# DRUM_1_MAIN_6.net
KiCad netlist of a schematic drawn in EAGLE
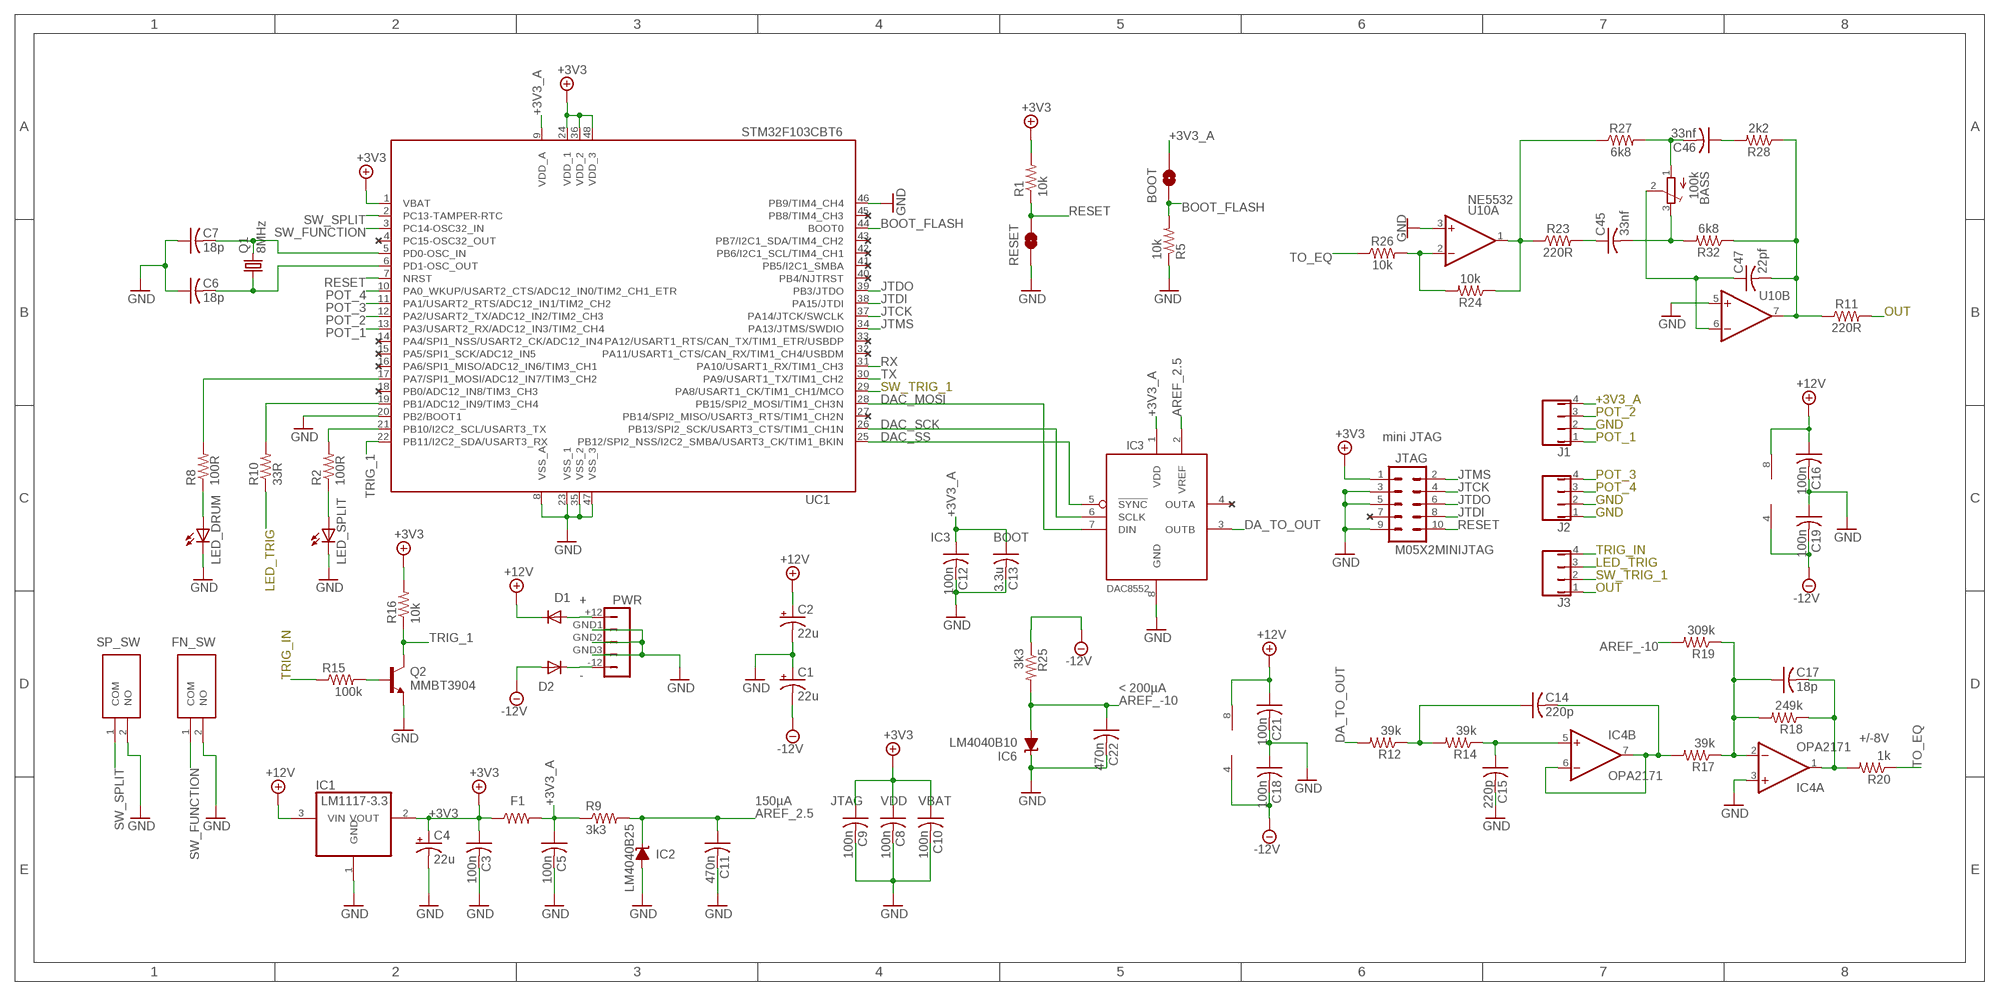
[diagram p0: schematic, sheet 1]

(export (version "E")
  (design (tool "Eeschema 10.0.6"))
  (components
    (comp (ref "BASS")
      (value "100k")
      (footprint "eagle-import:ADAFRUIT_TC33X")
      (libsource (lib "eagle-import") (part "ADAFRUIT_TRIMPOTTC33X"))
    )
    (comp (ref "BOOT")
      (value "BOOT")
      (footprint "eagle-import:SMT-JUMPER_2_NO_SILK")
      (libsource (lib "eagle-import") (part "JUMPER-SMT_2_NO_SILK"))
    )
    (comp (ref "C1")
      (value "22u")
      (footprint "eagle-import:PANASONIC_C")
      (libsource (lib "eagle-import") (part "CPOL-USC"))
    )
    (comp (ref "C2")
      (value "22u")
      (footprint "eagle-import:PANASONIC_C")
      (libsource (lib "eagle-import") (part "CPOL-USC"))
    )
    (comp (ref "C3")
      (value "100n")
      (footprint "eagle-import:C0603")
      (libsource (lib "eagle-import") (part "AA_Stobbert_1_C-USC0603"))
    )
    (comp (ref "C4")
      (value "22u")
      (footprint "eagle-import:PANASONIC_C")
      (libsource (lib "eagle-import") (part "CPOL-USC"))
    )
    (comp (ref "C5")
      (value "100n")
      (footprint "eagle-import:C0603")
      (libsource (lib "eagle-import") (part "AA_Stobbert_1_C-USC0603"))
    )
    (comp (ref "C6")
      (value "18p")
      (footprint "eagle-import:C0603")
      (libsource (lib "eagle-import") (part "AA_Stobbert_1_C-USC0603"))
    )
    (comp (ref "C7")
      (value "18p")
      (footprint "eagle-import:C0603")
      (libsource (lib "eagle-import") (part "AA_Stobbert_1_C-USC0603"))
    )
    (comp (ref "C8")
      (value "100n")
      (footprint "eagle-import:C0603")
      (libsource (lib "eagle-import") (part "AA_Stobbert_1_C-USC0603"))
    )
    (comp (ref "C9")
      (value "100n")
      (footprint "eagle-import:C0603")
      (libsource (lib "eagle-import") (part "AA_Stobbert_1_C-USC0603"))
    )
    (comp (ref "C10")
      (value "100n")
      (footprint "eagle-import:C0603")
      (libsource (lib "eagle-import") (part "AA_Stobbert_1_C-USC0603"))
    )
    (comp (ref "C11")
      (value "470n")
      (footprint "eagle-import:C0603")
      (libsource (lib "eagle-import") (part "AA_Stobbert_1_C-USC0603"))
    )
    (comp (ref "C12")
      (value "100n")
      (footprint "eagle-import:C0603")
      (libsource (lib "eagle-import") (part "AA_Stobbert_1_C-USC0603"))
    )
    (comp (ref "C13")
      (value "3.3u")
      (footprint "eagle-import:C0805K")
      (libsource (lib "eagle-import") (part "AA_Stobbert_1_C-USC0805K"))
    )
    (comp (ref "C14")
      (value "220p")
      (footprint "eagle-import:C0603")
      (libsource (lib "eagle-import") (part "AA_Stobbert_1_C-USC0603"))
    )
    (comp (ref "C15")
      (value "220p")
      (footprint "eagle-import:C0603")
      (libsource (lib "eagle-import") (part "AA_Stobbert_1_C-USC0603"))
    )
    (comp (ref "C16")
      (value "100n")
      (footprint "eagle-import:C0603")
      (libsource (lib "eagle-import") (part "AA_Stobbert_1_C-USC0603"))
    )
    (comp (ref "C17")
      (value "18p")
      (footprint "eagle-import:C0603")
      (libsource (lib "eagle-import") (part "AA_Stobbert_1_C-USC0603"))
    )
    (comp (ref "C18")
      (value "100n")
      (footprint "eagle-import:C0603")
      (libsource (lib "eagle-import") (part "AA_Stobbert_1_C-USC0603"))
    )
    (comp (ref "C19")
      (value "100n")
      (footprint "eagle-import:C0603")
      (libsource (lib "eagle-import") (part "AA_Stobbert_1_C-USC0603"))
    )
    (comp (ref "C21")
      (value "100n")
      (footprint "eagle-import:C0603")
      (libsource (lib "eagle-import") (part "AA_Stobbert_1_C-USC0603"))
    )
    (comp (ref "C22")
      (value "470n")
      (footprint "eagle-import:C0603")
      (libsource (lib "eagle-import") (part "AA_Stobbert_1_C-USC0603"))
    )
    (comp (ref "C45")
      (value "33nf")
      (footprint "eagle-import:C0603")
      (libsource (lib "eagle-import") (part "C-USC0603"))
    )
    (comp (ref "C46")
      (value "33nf")
      (footprint "eagle-import:C0603")
      (libsource (lib "eagle-import") (part "AA_Stobbert_1_C-USC0603"))
    )
    (comp (ref "C47")
      (value "22pf")
      (footprint "eagle-import:C0603")
      (libsource (lib "eagle-import") (part "C-USC0603"))
    )
    (comp (ref "D1")
      (value "1N5819HW")
      (footprint "eagle-import:PNS40010ER_SOD123W")
      (libsource (lib "eagle-import") (part "PWR_DIODE"))
    )
    (comp (ref "D2")
      (value "1N5819HW")
      (footprint "eagle-import:PNS40010ER_SOD123W")
      (libsource (lib "eagle-import") (part "PWR_DIODE"))
    )
    (comp (ref "F1")
      (value "742792693")
      (footprint "eagle-import:R0603")
      (libsource (lib "eagle-import") (part "R-US_R0603"))
    )
    (comp (ref "FN_SW")
      (value "PTS636_SM25_SMTR_LFS C778169")
      (footprint "eagle-import:PTS636SM25SMTRLFS")
      (fields
        (field (name "MANUFACTURER_PART_NUMBER") "PTS636 SM25 SMTR LFS")
        (field (name "MOUSER_PART_NUMBER") "611-PTS636SM25SMTRLF")
      )
      (libsource (lib "eagle-import") (part "PTS636_SM25_SMTR_LFS"))
    )
    (comp (ref "IC1")
      (value "LM1117-3.3")
      (footprint "eagle-import:SOT223")
      (libsource (lib "eagle-import") (part "REG1117"))
    )
    (comp (ref "IC2")
      (value "LM4040B25")
      (footprint "eagle-import:DBZ_R-PDSO-G3")
      (libsource (lib "eagle-import") (part "LM4041DBZB12"))
    )
    (comp (ref "IC3")
      (value "DAC8552")
      (footprint "eagle-import:MSOP-8")
      (libsource (lib "eagle-import") (part "DAC8552"))
    )
    (comp (ref "IC4")
      (value "OPA2171")
      (footprint "eagle-import:SO08")
      (libsource (lib "eagle-import") (part "linear_TL072D"))
    )
    (comp (ref "IC6")
      (value "LM4040B10")
      (footprint "eagle-import:DBZ_R-PDSO-G3")
      (libsource (lib "eagle-import") (part "LM4041DBZB12"))
    )
    (comp (ref "J1")
      (value "1x4 FEMALE HEADER")
      (footprint "eagle-import:JMP_4P_SIP")
      (libsource (lib "eagle-import") (part "JMP/4P/SIP"))
    )
    (comp (ref "J2")
      (value "1x4 FEMALE HEADER")
      (footprint "eagle-import:JMP_4P_SIP")
      (libsource (lib "eagle-import") (part "JMP/4P/SIP"))
    )
    (comp (ref "J3")
      (value "1x4 FEMALE HEADER")
      (footprint "eagle-import:JMP_4P_SIP")
      (libsource (lib "eagle-import") (part "JMP/4P/SIP"))
    )
    (comp (ref "JTAG")
      (value "M05X2MINIJTAG")
      (footprint "eagle-import:2X5-1.27")
      (libsource (lib "eagle-import") (part "M05X2MINIJTAG"))
    )
    (comp (ref "LED_DRUM")
      (value "LEDS0805")
      (footprint "eagle-import:LED_0805A")
      (libsource (lib "eagle-import") (part "LEDS0805"))
    )
    (comp (ref "LED_SPLIT")
      (value "LEDS0805")
      (footprint "eagle-import:LED_0805A")
      (libsource (lib "eagle-import") (part "LEDS0805"))
    )
    (comp (ref "PWR")
      (value "JMP/5P/DIP1X5_HEADER")
      (footprint "eagle-import:JMP_5P_DIP")
      (libsource (lib "eagle-import") (part "JMP/5P/DIP1X5_HEADER"))
    )
    (comp (ref "Q1")
      (value "8MHz")
      (footprint "eagle-import:HC49UP")
      (libsource (lib "eagle-import") (part "CRYSTALHC49UP"))
    )
    (comp (ref "Q2")
      (value "MMBT3904")
      (footprint "eagle-import:SOT23-BEC")
      (libsource (lib "eagle-import") (part "-NPN-SOT23-BECMMBT3904LT1"))
    )
    (comp (ref "R1")
      (value "10k")
      (footprint "eagle-import:R0603")
      (libsource (lib "eagle-import") (part "R-US_R0603"))
    )
    (comp (ref "R2")
      (value "100R")
      (footprint "eagle-import:R0603")
      (libsource (lib "eagle-import") (part "R-US_R0603"))
    )
    (comp (ref "R5")
      (value "10k")
      (footprint "eagle-import:R0603")
      (libsource (lib "eagle-import") (part "R-US_R0603"))
    )
    (comp (ref "R8")
      (value "100R")
      (footprint "eagle-import:R0603")
      (libsource (lib "eagle-import") (part "R-US_R0603"))
    )
    (comp (ref "R9")
      (value "3k3")
      (footprint "eagle-import:R0603")
      (libsource (lib "eagle-import") (part "R-US_R0603"))
    )
    (comp (ref "R10")
      (value "33R")
      (footprint "eagle-import:R0603")
      (libsource (lib "eagle-import") (part "R-US_R0603"))
    )
    (comp (ref "R11")
      (value "220R")
      (footprint "eagle-import:R0603")
      (libsource (lib "eagle-import") (part "R-US_R0603"))
    )
    (comp (ref "R12")
      (value "39k")
      (footprint "eagle-import:R0603")
      (libsource (lib "eagle-import") (part "R-US_R0603"))
    )
    (comp (ref "R14")
      (value "39k")
      (footprint "eagle-import:R0603")
      (libsource (lib "eagle-import") (part "R-US_R0603"))
    )
    (comp (ref "R15")
      (value "100k")
      (footprint "eagle-import:R0603")
      (libsource (lib "eagle-import") (part "R-US_R0603"))
    )
    (comp (ref "R16")
      (value "10k")
      (footprint "eagle-import:R0603")
      (libsource (lib "eagle-import") (part "R-US_R0603"))
    )
    (comp (ref "R17")
      (value "39k")
      (footprint "eagle-import:R0603")
      (libsource (lib "eagle-import") (part "R-US_R0603"))
    )
    (comp (ref "R18")
      (value "249k")
      (footprint "eagle-import:R0603")
      (libsource (lib "eagle-import") (part "R-US_R0603"))
    )
    (comp (ref "R19")
      (value "309k")
      (footprint "eagle-import:R0603")
      (libsource (lib "eagle-import") (part "R-US_R0603"))
    )
    (comp (ref "R20")
      (value "1k")
      (footprint "eagle-import:R0603")
      (libsource (lib "eagle-import") (part "R-US_R0603"))
    )
    (comp (ref "R23")
      (value "220R")
      (footprint "eagle-import:R0603")
      (libsource (lib "eagle-import") (part "R-US_R0603"))
    )
    (comp (ref "R24")
      (value "10k")
      (footprint "eagle-import:R0603")
      (libsource (lib "eagle-import") (part "R-US_R0603"))
    )
    (comp (ref "R25")
      (value "3k3")
      (footprint "eagle-import:R0603")
      (libsource (lib "eagle-import") (part "R-US_R0603"))
    )
    (comp (ref "R26")
      (value "10k")
      (footprint "eagle-import:R0603")
      (libsource (lib "eagle-import") (part "R-US_R0603"))
    )
    (comp (ref "R27")
      (value "6k8")
      (footprint "eagle-import:R0603")
      (libsource (lib "eagle-import") (part "R-US_R0603"))
    )
    (comp (ref "R28")
      (value "2k2")
      (footprint "eagle-import:R0603")
      (libsource (lib "eagle-import") (part "R-US_R0603"))
    )
    (comp (ref "R32")
      (value "6k8")
      (footprint "eagle-import:R0603")
      (libsource (lib "eagle-import") (part "R-US_R0603"))
    )
    (comp (ref "RESET")
      (value "RESET")
      (footprint "eagle-import:SMT-JUMPER_2_NO_SILK")
      (libsource (lib "eagle-import") (part "JUMPER-SMT_2_NO_SILK"))
    )
    (comp (ref "SP_SW")
      (value "PTS636_SM25_SMTR_LFS C778169")
      (footprint "eagle-import:PTS636SM25SMTRLFS")
      (fields
        (field (name "MANUFACTURER_PART_NUMBER") "PTS636 SM25 SMTR LFS")
        (field (name "MOUSER_PART_NUMBER") "611-PTS636SM25SMTRLF")
      )
      (libsource (lib "eagle-import") (part "PTS636_SM25_SMTR_LFS"))
    )
    (comp (ref "U10")
      (value "NE5532")
      (footprint "eagle-import:SO08")
      (libsource (lib "eagle-import") (part "TL072D"))
    )
    (comp (ref "UC1")
      (value "STM32F103CBT6")
      (footprint "eagle-import:LQFP48")
      (libsource (lib "eagle-import") (part "STM32F103CB"))
    )
  )
  (nets
    (net (code "1") (name "+3V3") (class "Default")
      (node (ref "C10") (pin "1") (pinfunction "1_1") (pintype "passive"))
      (node (ref "C3") (pin "1") (pinfunction "1_1") (pintype "passive"))
      (node (ref "C4") (pin "+") (pinfunction "+_+") (pintype "passive"))
      (node (ref "C8") (pin "1") (pinfunction "1_1") (pintype "passive"))
      (node (ref "C9") (pin "1") (pinfunction "1_1") (pintype "passive"))
      (node (ref "F1") (pin "1") (pinfunction "1_1") (pintype "passive"))
      (node (ref "IC1") (pin "2") (pinfunction "VOUT_2") (pintype "output"))
      (node (ref "JTAG") (pin "1") (pinfunction "1_1") (pintype "passive"))
      (node (ref "R1") (pin "2") (pinfunction "2_2") (pintype "passive"))
      (node (ref "R16") (pin "2") (pinfunction "2_2") (pintype "passive"))
      (node (ref "UC1") (pin "1") (pinfunction "VBAT_1") (pintype "power_in"))
      (node (ref "UC1") (pin "24") (pinfunction "VDD_1_24") (pintype "power_in"))
      (node (ref "UC1") (pin "36") (pinfunction "VDD_2_36") (pintype "power_in"))
      (node (ref "UC1") (pin "48") (pinfunction "VDD_3_48") (pintype "power_in"))
    )
    (net (code "2") (name "+12V") (class "Default")
      (node (ref "C16") (pin "1") (pinfunction "1_1") (pintype "passive"))
      (node (ref "C2") (pin "+") (pinfunction "+_+") (pintype "passive"))
      (node (ref "C21") (pin "1") (pinfunction "1_1") (pintype "passive"))
      (node (ref "D1") (pin "1") (pinfunction "K_1") (pintype "passive"))
      (node (ref "IC1") (pin "3") (pinfunction "VIN_3") (pintype "input"))
      (node (ref "IC4") (pin "8") (pinfunction "V+_8") (pintype "power_in"))
      (node (ref "U10") (pin "8") (pinfunction "V+_8") (pintype "power_in"))
    )
    (net (code "3") (name "-12V") (class "Default")
      (node (ref "C1") (pin "-") (pinfunction "-_-") (pintype "passive"))
      (node (ref "C18") (pin "2") (pinfunction "2_2") (pintype "passive"))
      (node (ref "C19") (pin "2") (pinfunction "2_2") (pintype "passive"))
      (node (ref "D2") (pin "2") (pinfunction "A_2") (pintype "passive"))
      (node (ref "IC4") (pin "4") (pinfunction "V-_4") (pintype "power_in"))
      (node (ref "R25") (pin "1") (pinfunction "1_1") (pintype "passive"))
      (node (ref "U10") (pin "4") (pinfunction "V-_4") (pintype "power_in"))
    )
    (net (code "4") (name "/+") (class "Default")
      (node (ref "D1") (pin "2") (pinfunction "A_2") (pintype "passive"))
      (node (ref "PWR") (pin "+12") (pinfunction "+12_+12") (pintype "passive"))
    )
    (net (code "5") (name "/+3V3_A") (class "Default")
      (node (ref "BOOT") (pin "2") (pinfunction "2_2") (pintype "passive"))
      (node (ref "C12") (pin "1") (pinfunction "1_1") (pintype "passive"))
      (node (ref "C13") (pin "1") (pinfunction "1_1") (pintype "passive"))
      (node (ref "C5") (pin "1") (pinfunction "1_1") (pintype "passive"))
      (node (ref "F1") (pin "2") (pinfunction "2_2") (pintype "passive"))
      (node (ref "IC3") (pin "1") (pinfunction "VDD_1") (pintype "power_in"))
      (node (ref "J1") (pin "4") (pinfunction "4_4") (pintype "passive"))
      (node (ref "R9") (pin "1") (pinfunction "1_1") (pintype "passive"))
      (node (ref "UC1") (pin "9") (pinfunction "VDD_A_9") (pintype "power_in"))
    )
    (net (code "6") (name "/-") (class "Default")
      (node (ref "D2") (pin "1") (pinfunction "K_1") (pintype "passive"))
      (node (ref "PWR") (pin "-12") (pinfunction "-12_-12") (pintype "passive"))
    )
    (net (code "7") (name "/AREF_-10") (class "Default")
      (node (ref "C22") (pin "1") (pinfunction "1_1") (pintype "passive"))
      (node (ref "IC6") (pin "2") (pinfunction "A_2") (pintype "passive"))
      (node (ref "R19") (pin "2") (pinfunction "2_2") (pintype "passive"))
      (node (ref "R25") (pin "2") (pinfunction "2_2") (pintype "passive"))
    )
    (net (code "8") (name "/AREF_2.5") (class "Default")
      (node (ref "C11") (pin "1") (pinfunction "1_1") (pintype "passive"))
      (node (ref "IC2") (pin "1") (pinfunction "C_1") (pintype "passive"))
      (node (ref "IC3") (pin "2") (pinfunction "VREF_2") (pintype "power_in"))
      (node (ref "R9") (pin "2") (pinfunction "2_2") (pintype "passive"))
    )
    (net (code "9") (name "/BOOT_FLASH") (class "Default")
      (node (ref "BOOT") (pin "1") (pinfunction "1_1") (pintype "passive"))
      (node (ref "R5") (pin "2") (pinfunction "2_2") (pintype "passive"))
      (node (ref "UC1") (pin "44") (pinfunction "BOOT0_44") (pintype "input"))
    )
    (net (code "10") (name "/DAC_MOSI") (class "Default")
      (node (ref "IC3") (pin "7") (pinfunction "DIN_7") (pintype "bidirectional"))
      (node (ref "UC1") (pin "28") (pinfunction "PB15/SPI2_MOSI/TIM1_CH3N_28") (pintype "input"))
    )
    (net (code "11") (name "/DAC_SCK") (class "Default")
      (node (ref "IC3") (pin "6") (pinfunction "SCLK_6") (pintype "bidirectional"))
      (node (ref "UC1") (pin "26") (pinfunction "PB13/SPI2_SCK/USART3_CTS/TIM1_CH1N_26") (pintype "input"))
    )
    (net (code "12") (name "/DAC_SS") (class "Default")
      (node (ref "IC3") (pin "5") (pinfunction "~{SYNC}_5") (pintype "bidirectional"))
      (node (ref "UC1") (pin "25") (pinfunction "PB12/SPI2_NSS/I2C2_SMBA/USART3_CK/TIM1_BKIN_25") (pintype "input"))
    )
    (net (code "13") (name "/DA_TO_OUT") (class "Default")
      (node (ref "IC3") (pin "3") (pinfunction "OUTB_3") (pintype "input"))
      (node (ref "R12") (pin "2") (pinfunction "2_2") (pintype "passive"))
    )
    (net (code "14") (name "/JTCK") (class "Default")
      (node (ref "JTAG") (pin "4") (pinfunction "4_4") (pintype "passive"))
      (node (ref "UC1") (pin "37") (pinfunction "PA14/JTCK/SWCLK_37") (pintype "bidirectional"))
    )
    (net (code "15") (name "/JTDI") (class "Default")
      (node (ref "JTAG") (pin "8") (pinfunction "8_8") (pintype "passive"))
      (node (ref "UC1") (pin "38") (pinfunction "PA15/JTDI_38") (pintype "bidirectional"))
    )
    (net (code "16") (name "/JTDO") (class "Default")
      (node (ref "JTAG") (pin "6") (pinfunction "6_6") (pintype "passive"))
      (node (ref "UC1") (pin "39") (pinfunction "PB3/JTDO_39") (pintype "bidirectional"))
    )
    (net (code "17") (name "/JTMS") (class "Default")
      (node (ref "JTAG") (pin "2") (pinfunction "2_2") (pintype "passive"))
      (node (ref "UC1") (pin "34") (pinfunction "PA13/JTMS/SWDIO_34") (pintype "bidirectional"))
    )
    (net (code "18") (name "/LED_TRIG") (class "Default")
      (node (ref "J3") (pin "3") (pinfunction "3_3") (pintype "passive"))
      (node (ref "R10") (pin "1") (pinfunction "1_1") (pintype "passive"))
    )
    (net (code "19") (name "/OUT") (class "Default")
      (node (ref "J3") (pin "1") (pinfunction "1_1") (pintype "passive"))
      (node (ref "R11") (pin "2") (pinfunction "2_2") (pintype "passive"))
    )
    (net (code "20") (name "/POT_1") (class "Default")
      (node (ref "J1") (pin "1") (pinfunction "1_1") (pintype "passive"))
      (node (ref "UC1") (pin "13") (pinfunction "PA3/USART2_RX/ADC12_IN3/TIM2_CH4_13") (pintype "bidirectional"))
    )
    (net (code "21") (name "/POT_2") (class "Default")
      (node (ref "J1") (pin "3") (pinfunction "3_3") (pintype "passive"))
      (node (ref "UC1") (pin "12") (pinfunction "PA2/USART2_TX/ADC12_IN2/TIM2_CH3_12") (pintype "bidirectional"))
    )
    (net (code "22") (name "/POT_3") (class "Default")
      (node (ref "J2") (pin "4") (pinfunction "4_4") (pintype "passive"))
      (node (ref "UC1") (pin "11") (pinfunction "PA1/USART2_RTS/ADC12_IN1/TIM2_CH2_11") (pintype "bidirectional"))
    )
    (net (code "23") (name "/POT_4") (class "Default")
      (node (ref "J2") (pin "3") (pinfunction "3_3") (pintype "passive"))
      (node (ref "UC1") (pin "10") (pinfunction "PA0_WKUP/USART2_CTS/ADC12_IN0/TIM2_CH1_ETR_10") (pintype "bidirectional"))
    )
    (net (code "24") (name "/RESET") (class "Default")
      (node (ref "JTAG") (pin "10") (pinfunction "10_10") (pintype "passive"))
      (node (ref "R1") (pin "1") (pinfunction "1_1") (pintype "passive"))
      (node (ref "RESET") (pin "2") (pinfunction "2_2") (pintype "passive"))
      (node (ref "UC1") (pin "7") (pinfunction "NRST_7") (pintype "input"))
    )
    (net (code "25") (name "/RX") (class "Default")
      (node (ref "UC1") (pin "31") (pinfunction "PA10/USART1_RX/TIM1_CH3_31") (pintype "bidirectional"))
    )
    (net (code "26") (name "/SW_FUNCTION") (class "Default")
      (node (ref "FN_SW") (pin "1") (pinfunction "COM_1") (pintype "bidirectional"))
      (node (ref "UC1") (pin "3") (pinfunction "PC14-OSC32_IN_3") (pintype "input"))
    )
    (net (code "27") (name "/SW_SPLIT") (class "Default")
      (node (ref "SP_SW") (pin "1") (pinfunction "COM_1") (pintype "bidirectional"))
      (node (ref "UC1") (pin "2") (pinfunction "PC13-TAMPER-RTC_2") (pintype "input"))
    )
    (net (code "28") (name "/SW_TRIG_1") (class "Default")
      (node (ref "J3") (pin "2") (pinfunction "2_2") (pintype "passive"))
      (node (ref "UC1") (pin "29") (pinfunction "PA8/USART1_CK/TIM1_CH1/MCO_29") (pintype "bidirectional"))
    )
    (net (code "29") (name "/TO_EQ") (class "Default")
      (node (ref "R20") (pin "1") (pinfunction "1_1") (pintype "passive"))
      (node (ref "R26") (pin "1") (pinfunction "1_1") (pintype "passive"))
    )
    (net (code "30") (name "/TRIG_1") (class "Default")
      (node (ref "Q2") (pin "C") (pinfunction "C_C") (pintype "passive"))
      (node (ref "R16") (pin "1") (pinfunction "1_1") (pintype "passive"))
      (node (ref "UC1") (pin "22") (pinfunction "PB11/I2C2_SDA/USART3_RX_22") (pintype "input"))
    )
    (net (code "31") (name "/TRIG_IN") (class "Default")
      (node (ref "J3") (pin "4") (pinfunction "4_4") (pintype "passive"))
      (node (ref "R15") (pin "1") (pinfunction "1_1") (pintype "passive"))
    )
    (net (code "32") (name "/TX") (class "Default")
      (node (ref "UC1") (pin "30") (pinfunction "PA9/USART1_TX/TIM1_CH2_30") (pintype "input"))
    )
    (net (code "33") (name "GND") (class "Default")
      (node (ref "C1") (pin "+") (pinfunction "+_+") (pintype "passive"))
      (node (ref "C10") (pin "2") (pinfunction "2_2") (pintype "passive"))
      (node (ref "C11") (pin "2") (pinfunction "2_2") (pintype "passive"))
      (node (ref "C12") (pin "2") (pinfunction "2_2") (pintype "passive"))
      (node (ref "C13") (pin "2") (pinfunction "2_2") (pintype "passive"))
      (node (ref "C15") (pin "2") (pinfunction "2_2") (pintype "passive"))
      (node (ref "C16") (pin "2") (pinfunction "2_2") (pintype "passive"))
      (node (ref "C18") (pin "1") (pinfunction "1_1") (pintype "passive"))
      (node (ref "C19") (pin "1") (pinfunction "1_1") (pintype "passive"))
      (node (ref "C2") (pin "-") (pinfunction "-_-") (pintype "passive"))
      (node (ref "C21") (pin "2") (pinfunction "2_2") (pintype "passive"))
      (node (ref "C22") (pin "2") (pinfunction "2_2") (pintype "passive"))
      (node (ref "C3") (pin "2") (pinfunction "2_2") (pintype "passive"))
      (node (ref "C4") (pin "-") (pinfunction "-_-") (pintype "passive"))
      (node (ref "C5") (pin "2") (pinfunction "2_2") (pintype "passive"))
      (node (ref "C6") (pin "1") (pinfunction "1_1") (pintype "passive"))
      (node (ref "C7") (pin "1") (pinfunction "1_1") (pintype "passive"))
      (node (ref "C8") (pin "2") (pinfunction "2_2") (pintype "passive"))
      (node (ref "C9") (pin "2") (pinfunction "2_2") (pintype "passive"))
      (node (ref "FN_SW") (pin "2") (pinfunction "NO_2") (pintype "bidirectional"))
      (node (ref "IC1") (pin "1") (pinfunction "GND_1") (pintype "power_in"))
      (node (ref "IC2") (pin "2") (pinfunction "A_2") (pintype "passive"))
      (node (ref "IC3") (pin "8") (pinfunction "GND_8") (pintype "power_in"))
      (node (ref "IC4") (pin "3") (pinfunction "+IN_3") (pintype "input"))
      (node (ref "IC6") (pin "1") (pinfunction "C_1") (pintype "passive"))
      (node (ref "J1") (pin "2") (pinfunction "2_2") (pintype "passive"))
      (node (ref "J2") (pin "1") (pinfunction "1_1") (pintype "passive"))
      (node (ref "J2") (pin "2") (pinfunction "2_2") (pintype "passive"))
      (node (ref "JTAG") (pin "3") (pinfunction "3_3") (pintype "passive"))
      (node (ref "JTAG") (pin "5") (pinfunction "5_5") (pintype "passive"))
      (node (ref "JTAG") (pin "9") (pinfunction "9_9") (pintype "passive"))
      (node (ref "LED_DRUM") (pin "-") (pinfunction "C_-") (pintype "passive"))
      (node (ref "LED_SPLIT") (pin "-") (pinfunction "C_-") (pintype "passive"))
      (node (ref "PWR") (pin "GND1") (pinfunction "GND1_GND1") (pintype "passive"))
      (node (ref "PWR") (pin "GND2") (pinfunction "GND2_GND2") (pintype "passive"))
      (node (ref "PWR") (pin "GND3") (pinfunction "GND3_GND3") (pintype "passive"))
      (node (ref "Q2") (pin "E") (pinfunction "E_E") (pintype "passive"))
      (node (ref "R5") (pin "1") (pinfunction "1_1") (pintype "passive"))
      (node (ref "RESET") (pin "1") (pinfunction "1_1") (pintype "passive"))
      (node (ref "SP_SW") (pin "2") (pinfunction "NO_2") (pintype "bidirectional"))
      (node (ref "U10") (pin "3") (pinfunction "+IN_3") (pintype "input"))
      (node (ref "U10") (pin "5") (pinfunction "+IN_5") (pintype "input"))
      (node (ref "UC1") (pin "20") (pinfunction "PB2/BOOT1_20") (pintype "bidirectional"))
      (node (ref "UC1") (pin "23") (pinfunction "VSS_1_23") (pintype "power_in"))
      (node (ref "UC1") (pin "35") (pinfunction "VSS_2_35") (pintype "power_in"))
      (node (ref "UC1") (pin "46") (pinfunction "PB9/TIM4_CH4_46") (pintype "input"))
      (node (ref "UC1") (pin "47") (pinfunction "VSS_3_47") (pintype "power_in"))
      (node (ref "UC1") (pin "8") (pinfunction "VSS_A_8") (pintype "power_in"))
    )
    (net (code "34") (name "Net-(BASS-Pad1)") (class "Default")
      (node (ref "BASS") (pin "1") (pinfunction "1_1") (pintype "passive"))
      (node (ref "C46") (pin "2") (pinfunction "2_2") (pintype "passive"))
      (node (ref "R27") (pin "2") (pinfunction "2_2") (pintype "passive"))
    )
    (net (code "35") (name "Net-(BASS-Pad3)") (class "Default")
      (node (ref "BASS") (pin "3") (pinfunction "3_3") (pintype "passive"))
      (node (ref "C45") (pin "2") (pinfunction "2_2") (pintype "passive"))
      (node (ref "R32") (pin "2") (pinfunction "2_2") (pintype "passive"))
    )
    (net (code "36") (name "Net-(C14-Pad1)") (class "Default")
      (node (ref "C14") (pin "1") (pinfunction "1_1") (pintype "passive"))
      (node (ref "R12") (pin "1") (pinfunction "1_1") (pintype "passive"))
      (node (ref "R14") (pin "2") (pinfunction "2_2") (pintype "passive"))
    )
    (net (code "37") (name "Net-(C45-Pad1)") (class "Default")
      (node (ref "C45") (pin "1") (pinfunction "1_1") (pintype "passive"))
      (node (ref "R23") (pin "2") (pinfunction "2_2") (pintype "passive"))
    )
    (net (code "38") (name "Net-(C46-Pad1)") (class "Default")
      (node (ref "C46") (pin "1") (pinfunction "1_1") (pintype "passive"))
      (node (ref "R28") (pin "2") (pinfunction "2_2") (pintype "passive"))
    )
    (net (code "39") (name "Net-(IC4A--IN)") (class "Default")
      (node (ref "C17") (pin "1") (pinfunction "1_1") (pintype "passive"))
      (node (ref "IC4") (pin "2") (pinfunction "-IN_2") (pintype "input"))
      (node (ref "R17") (pin "1") (pinfunction "1_1") (pintype "passive"))
      (node (ref "R18") (pin "2") (pinfunction "2_2") (pintype "passive"))
      (node (ref "R19") (pin "1") (pinfunction "1_1") (pintype "passive"))
    )
    (net (code "40") (name "Net-(IC4A-OUT)") (class "Default")
      (node (ref "C17") (pin "2") (pinfunction "2_2") (pintype "passive"))
      (node (ref "IC4") (pin "1") (pinfunction "OUT_1") (pintype "output"))
      (node (ref "R18") (pin "1") (pinfunction "1_1") (pintype "passive"))
      (node (ref "R20") (pin "2") (pinfunction "2_2") (pintype "passive"))
    )
    (net (code "41") (name "Net-(IC4B-+IN)") (class "Default")
      (node (ref "C15") (pin "1") (pinfunction "1_1") (pintype "passive"))
      (node (ref "IC4") (pin "5") (pinfunction "+IN_5") (pintype "input"))
      (node (ref "R14") (pin "1") (pinfunction "1_1") (pintype "passive"))
    )
    (net (code "42") (name "Net-(IC4B--IN)") (class "Default")
      (node (ref "C14") (pin "2") (pinfunction "2_2") (pintype "passive"))
      (node (ref "IC4") (pin "6") (pinfunction "-IN_6") (pintype "input"))
      (node (ref "IC4") (pin "7") (pinfunction "OUT_7") (pintype "output"))
      (node (ref "R17") (pin "2") (pinfunction "2_2") (pintype "passive"))
    )
    (net (code "43") (name "Net-(LED_DRUM-A)") (class "Default")
      (node (ref "LED_DRUM") (pin "+") (pinfunction "A_+") (pintype "passive"))
      (node (ref "R8") (pin "1") (pinfunction "1_1") (pintype "passive"))
    )
    (net (code "44") (name "Net-(LED_SPLIT-A)") (class "Default")
      (node (ref "LED_SPLIT") (pin "+") (pinfunction "A_+") (pintype "passive"))
      (node (ref "R2") (pin "1") (pinfunction "1_1") (pintype "passive"))
    )
    (net (code "45") (name "Net-(Q2-PadB)") (class "Default")
      (node (ref "Q2") (pin "B") (pinfunction "B_B") (pintype "passive"))
      (node (ref "R15") (pin "2") (pinfunction "2_2") (pintype "passive"))
    )
    (net (code "46") (name "Net-(U10A--IN)") (class "Default")
      (node (ref "R24") (pin "2") (pinfunction "2_2") (pintype "passive"))
      (node (ref "R26") (pin "2") (pinfunction "2_2") (pintype "passive"))
      (node (ref "U10") (pin "2") (pinfunction "-IN_2") (pintype "input"))
    )
    (net (code "47") (name "Net-(U10A-OUT)") (class "Default")
      (node (ref "R23") (pin "1") (pinfunction "1_1") (pintype "passive"))
      (node (ref "R24") (pin "1") (pinfunction "1_1") (pintype "passive"))
      (node (ref "R27") (pin "1") (pinfunction "1_1") (pintype "passive"))
      (node (ref "U10") (pin "1") (pinfunction "OUT_1") (pintype "output"))
    )
    (net (code "48") (name "Net-(U10B--IN)") (class "Default")
      (node (ref "BASS") (pin "2") (pinfunction "2_2") (pintype "passive"))
      (node (ref "C47") (pin "1") (pinfunction "1_1") (pintype "passive"))
      (node (ref "U10") (pin "6") (pinfunction "-IN_6") (pintype "input"))
    )
    (net (code "49") (name "Net-(U10B-OUT)") (class "Default")
      (node (ref "C47") (pin "2") (pinfunction "2_2") (pintype "passive"))
      (node (ref "R11") (pin "1") (pinfunction "1_1") (pintype "passive"))
      (node (ref "R28") (pin "1") (pinfunction "1_1") (pintype "passive"))
      (node (ref "R32") (pin "1") (pinfunction "1_1") (pintype "passive"))
      (node (ref "U10") (pin "7") (pinfunction "OUT_7") (pintype "output"))
    )
    (net (code "50") (name "Net-(UC1-PA7{slash}SPI1_MOSI{slash}ADC12_IN7{slash}TIM3_CH2)") (class "Default")
      (node (ref "R8") (pin "2") (pinfunction "2_2") (pintype "passive"))
      (node (ref "UC1") (pin "17") (pinfunction "PA7/SPI1_MOSI/ADC12_IN7/TIM3_CH2_17") (pintype "bidirectional"))
    )
    (net (code "51") (name "Net-(UC1-PB1{slash}ADC12_IN9{slash}TIM3_CH4)") (class "Default")
      (node (ref "R10") (pin "2") (pinfunction "2_2") (pintype "passive"))
      (node (ref "UC1") (pin "19") (pinfunction "PB1/ADC12_IN9/TIM3_CH4_19") (pintype "bidirectional"))
    )
    (net (code "52") (name "Net-(UC1-PB10{slash}I2C2_SCL{slash}USART3_TX)") (class "Default")
      (node (ref "R2") (pin "2") (pinfunction "2_2") (pintype "passive"))
      (node (ref "UC1") (pin "21") (pinfunction "PB10/I2C2_SCL/USART3_TX_21") (pintype "input"))
    )
    (net (code "53") (name "Net-(UC1-PD0-OSC_IN)") (class "Default")
      (node (ref "C7") (pin "2") (pinfunction "2_2") (pintype "passive"))
      (node (ref "Q1") (pin "2") (pinfunction "2_2") (pintype "passive"))
      (node (ref "UC1") (pin "5") (pinfunction "PD0-OSC_IN_5") (pintype "input"))
    )
    (net (code "54") (name "Net-(UC1-PD1-OSC_OUT)") (class "Default")
      (node (ref "C6") (pin "2") (pinfunction "2_2") (pintype "passive"))
      (node (ref "Q1") (pin "1") (pinfunction "1_1") (pintype "passive"))
      (node (ref "UC1") (pin "6") (pinfunction "PD1-OSC_OUT_6") (pintype "input"))
    )
    (net (code "55") (name "unconnected-(IC3-OUTA-Pad4)") (class "Default")
      (node (ref "IC3") (pin "4") (pinfunction "OUTA_4") (pintype "output"))
    )
    (net (code "56") (name "unconnected-(JTAG-Pad7)") (class "Default")
      (node (ref "JTAG") (pin "7") (pinfunction "7_7") (pintype "passive"))
    )
    (net (code "57") (name "unconnected-(UC1-PA4{slash}SPI1_NSS{slash}USART2_CK{slash}ADC12_IN4-Pad14)") (class "Default")
      (node (ref "UC1") (pin "14") (pinfunction "PA4/SPI1_NSS/USART2_CK/ADC12_IN4_14") (pintype "bidirectional"))
    )
    (net (code "58") (name "unconnected-(UC1-PA5{slash}SPI1_SCK{slash}ADC12_IN5-Pad15)") (class "Default")
      (node (ref "UC1") (pin "15") (pinfunction "PA5/SPI1_SCK/ADC12_IN5_15") (pintype "bidirectional"))
    )
    (net (code "59") (name "unconnected-(UC1-PA6{slash}SPI1_MISO{slash}ADC12_IN6{slash}TIM3_CH1-Pad16)") (class "Default")
      (node (ref "UC1") (pin "16") (pinfunction "PA6/SPI1_MISO/ADC12_IN6/TIM3_CH1_16") (pintype "bidirectional"))
    )
    (net (code "60") (name "unconnected-(UC1-PA11{slash}USART1_CTS{slash}CAN_RX{slash}TIM1_CH4{slash}USBDM-Pad32)") (class "Default")
      (node (ref "UC1") (pin "32") (pinfunction "PA11/USART1_CTS/CAN_RX/TIM1_CH4/USBDM_32") (pintype "bidirectional"))
    )
    (net (code "61") (name "unconnected-(UC1-PA12{slash}USART1_RTS{slash}CAN_TX{slash}TIM1_ETR{slash}USBDP-Pad33)") (class "Default")
      (node (ref "UC1") (pin "33") (pinfunction "PA12/USART1_RTS/CAN_TX/TIM1_ETR/USBDP_33") (pintype "bidirectional"))
    )
    (net (code "62") (name "unconnected-(UC1-PB0{slash}ADC12_IN8{slash}TIM3_CH3-Pad18)") (class "Default")
      (node (ref "UC1") (pin "18") (pinfunction "PB0/ADC12_IN8/TIM3_CH3_18") (pintype "bidirectional"))
    )
    (net (code "63") (name "unconnected-(UC1-PB4{slash}NJTRST-Pad40)") (class "Default")
      (node (ref "UC1") (pin "40") (pinfunction "PB4/NJTRST_40") (pintype "bidirectional"))
    )
    (net (code "64") (name "unconnected-(UC1-PB5{slash}I2C1_SMBA-Pad41)") (class "Default")
      (node (ref "UC1") (pin "41") (pinfunction "PB5/I2C1_SMBA_41") (pintype "input"))
    )
    (net (code "65") (name "unconnected-(UC1-PB6{slash}I2C1_SCL{slash}TIM4_CH1-Pad42)") (class "Default")
      (node (ref "UC1") (pin "42") (pinfunction "PB6/I2C1_SCL/TIM4_CH1_42") (pintype "input"))
    )
    (net (code "66") (name "unconnected-(UC1-PB7{slash}I2C1_SDA{slash}TIM4_CH2-Pad43)") (class "Default")
      (node (ref "UC1") (pin "43") (pinfunction "PB7/I2C1_SDA/TIM4_CH2_43") (pintype "bidirectional"))
    )
    (net (code "67") (name "unconnected-(UC1-PB8{slash}TIM4_CH3-Pad45)") (class "Default")
      (node (ref "UC1") (pin "45") (pinfunction "PB8/TIM4_CH3_45") (pintype "bidirectional"))
    )
    (net (code "68") (name "unconnected-(UC1-PB14{slash}SPI2_MISO{slash}USART3_RTS{slash}TIM1_CH2N-Pad27)") (class "Default")
      (node (ref "UC1") (pin "27") (pinfunction "PB14/SPI2_MISO/USART3_RTS/TIM1_CH2N_27") (pintype "input"))
    )
    (net (code "69") (name "unconnected-(UC1-PC15-OSC32_OUT-Pad4)") (class "Default")
      (node (ref "UC1") (pin "4") (pinfunction "PC15-OSC32_OUT_4") (pintype "input"))
    )
  )
)
